# ece411-t15-light-sensitive-alarm-clock.net
KiCad netlist of a schematic drawn in EAGLE
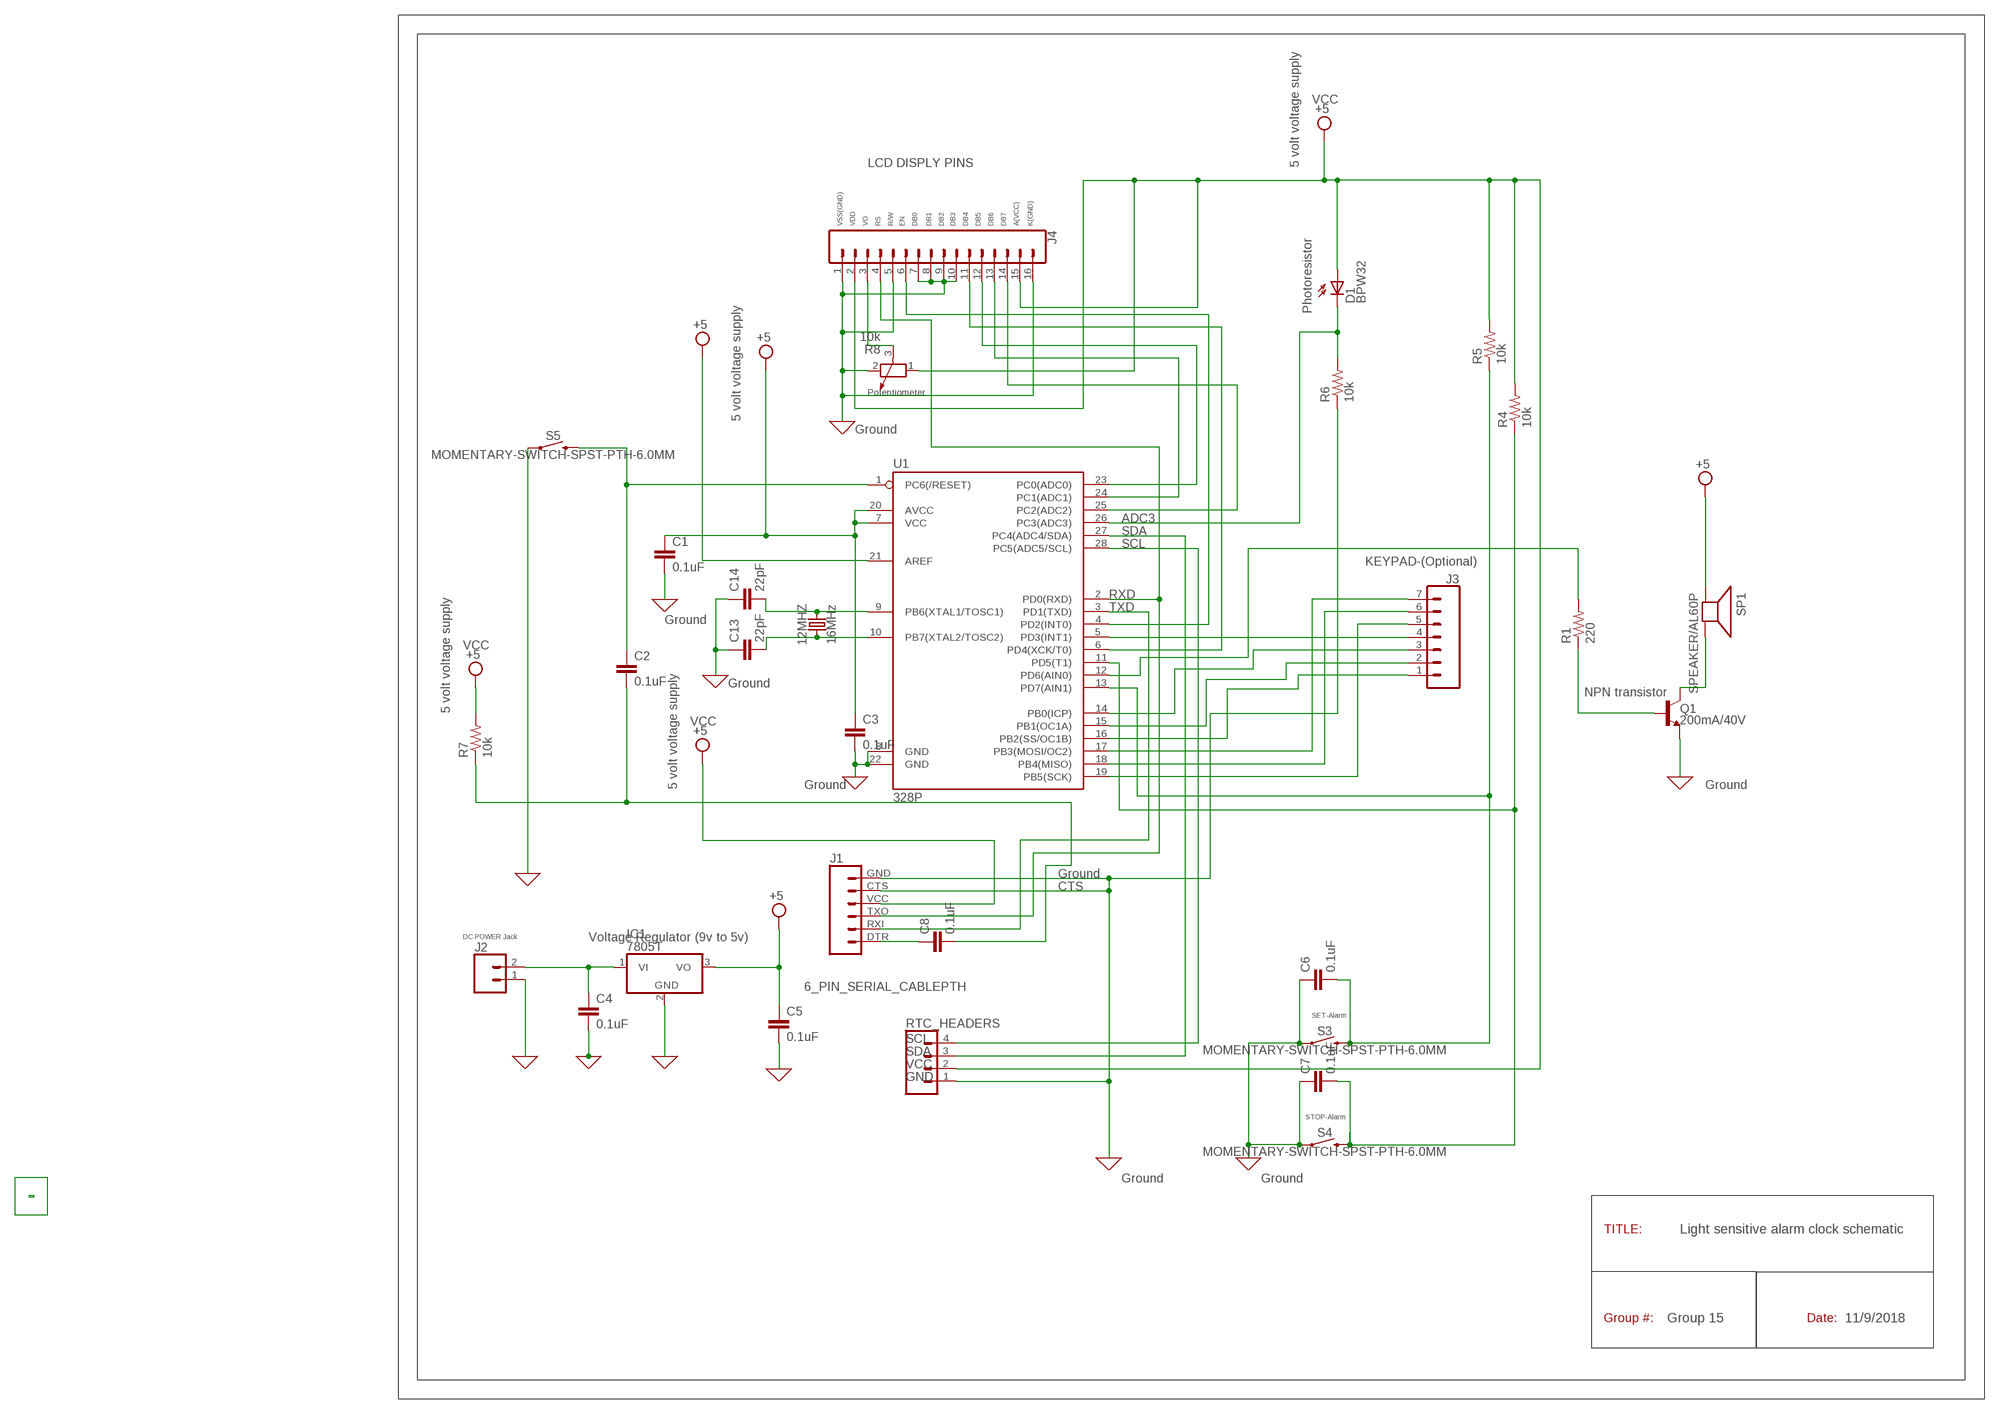
[diagram p0: schematic, sheet 1]

(export (version "E")
  (design (tool "Eeschema 10.0.6"))
  (components
    (comp (ref "12MHZ")
      (value "16MHz")
      (footprint "eagle-import:CRYSTAL-PTH-2X6-CYL")
      (libsource (lib "eagle-import") (part "CRYSTALPTH-2X6"))
    )
    (comp (ref "C1")
      (value "0.1uF")
      (footprint "eagle-import:0603")
      (libsource (lib "eagle-import") (part "0.1UF-0603-25V-(+80/-20%)"))
    )
    (comp (ref "C2")
      (value "0.1uF")
      (footprint "eagle-import:0603")
      (libsource (lib "eagle-import") (part "0.1UF-0603-25V-(+80/-20%)"))
    )
    (comp (ref "C3")
      (value "0.1uF")
      (footprint "eagle-import:0603")
      (libsource (lib "eagle-import") (part "0.1UF-0603-25V-(+80/-20%)"))
    )
    (comp (ref "C4")
      (value "0.1uF")
      (footprint "eagle-import:0603")
      (libsource (lib "eagle-import") (part "0.1UF-0603-25V-(+80/-20%)"))
    )
    (comp (ref "C5")
      (value "0.1uF")
      (footprint "eagle-import:0603")
      (libsource (lib "eagle-import") (part "0.1UF-0603-25V-(+80/-20%)"))
    )
    (comp (ref "C6")
      (value "0.1uF")
      (footprint "eagle-import:0603")
      (libsource (lib "eagle-import") (part "0.1UF-0603-25V-(+80/-20%)"))
    )
    (comp (ref "C7")
      (value "0.1uF")
      (footprint "eagle-import:0603")
      (libsource (lib "eagle-import") (part "0.1UF-0603-25V-(+80/-20%)"))
    )
    (comp (ref "C8")
      (value "0.1uF")
      (footprint "eagle-import:0603")
      (libsource (lib "eagle-import") (part "0.1UF-0603-25V-(+80/-20%)"))
    )
    (comp (ref "C13")
      (value "22pF")
      (footprint "eagle-import:0603")
      (libsource (lib "eagle-import") (part "22PF-0603-50V-5%"))
    )
    (comp (ref "C14")
      (value "22pF")
      (footprint "eagle-import:0603")
      (libsource (lib "eagle-import") (part "22PF-0603-50V-5%"))
    )
    (comp (ref "D1")
      (value "BPW32")
      (footprint "eagle-import:BPW32")
      (libsource (lib "eagle-import") (part "BPW32"))
    )
    (comp (ref "IC1")
      (value "7805T")
      (footprint "eagle-import:TO220H")
      (libsource (lib "eagle-import") (part "78T05"))
    )
    (comp (ref "J1")
      (value "6_PIN_SERIAL_CABLEPTH")
      (footprint "eagle-import:FTDI_BASIC")
      (libsource (lib "eagle-import") (part "6_PIN_SERIAL_CABLEPTH"))
    )
    (comp (ref "J2")
      (value "CONN_02")
      (footprint "eagle-import:1X02")
      (libsource (lib "eagle-import") (part "CONN_02"))
    )
    (comp (ref "J3")
      (value "CONN_07")
      (footprint "eagle-import:1X07")
      (libsource (lib "eagle-import") (part "CONN_07"))
    )
    (comp (ref "J4")
      (value "CONN_16")
      (footprint "eagle-import:1X16")
      (libsource (lib "eagle-import") (part "CONN_16"))
    )
    (comp (ref "Q1")
      (value "200mA/40V")
      (footprint "eagle-import:TO-92")
      (libsource (lib "eagle-import") (part "TRANS_NPN-2N3904"))
    )
    (comp (ref "R1")
      (value "220")
      (footprint "eagle-import:R0603")
      (libsource (lib "eagle-import") (part "R-US_R0603"))
    )
    (comp (ref "R4")
      (value "10k")
      (footprint "eagle-import:R0603")
      (libsource (lib "eagle-import") (part "R-US_R0603"))
    )
    (comp (ref "R5")
      (value "10k")
      (footprint "eagle-import:R0603")
      (libsource (lib "eagle-import") (part "R-US_R0603"))
    )
    (comp (ref "R6")
      (value "10k")
      (footprint "eagle-import:R0603")
      (libsource (lib "eagle-import") (part "R-US_R0603"))
    )
    (comp (ref "R7")
      (value "10k")
      (footprint "eagle-import:R0603")
      (libsource (lib "eagle-import") (part "R-US_R0603"))
    )
    (comp (ref "R8")
      (value "10k")
      (footprint "eagle-import:PT-10")
      (libsource (lib "eagle-import") (part "POTENTIOMETER_PT-10"))
    )
    (comp (ref "RTC_HEADERS")
      (value "CONN_04")
      (footprint "eagle-import:1X04")
      (libsource (lib "eagle-import") (part "CONN_04"))
    )
    (comp (ref "S3")
      (value "MOMENTARY-SWITCH-SPST-PTH-6.0MM")
      (footprint "eagle-import:TACTILE_SWITCH_PTH_6.0MM")
      (libsource (lib "eagle-import") (part "MOMENTARY-SWITCH-SPST-PTH-6.0MM"))
    )
    (comp (ref "S4")
      (value "MOMENTARY-SWITCH-SPST-PTH-6.0MM")
      (footprint "eagle-import:TACTILE_SWITCH_PTH_6.0MM")
      (libsource (lib "eagle-import") (part "MOMENTARY-SWITCH-SPST-PTH-6.0MM"))
    )
    (comp (ref "S5")
      (value "MOMENTARY-SWITCH-SPST-PTH-6.0MM")
      (footprint "eagle-import:TACTILE_SWITCH_PTH_6.0MM")
      (libsource (lib "eagle-import") (part "MOMENTARY-SWITCH-SPST-PTH-6.0MM"))
    )
    (comp (ref "SP1")
      (value "SPEAKER/AL60P")
      (footprint "eagle-import:AL60P")
      (libsource (lib "eagle-import") (part "SPEAKER/AL60P"))
    )
    (comp (ref "U1")
      (value "328P")
      (footprint "eagle-import:DIP28")
      (libsource (lib "eagle-import") (part "ATMEGA328P_PDIP"))
    )
  )
  (nets
    (net (code "1") (name "+5") (class "Default")
      (node (ref "C1") (pin "1") (pinfunction "1_1") (pintype "passive"))
      (node (ref "C3") (pin "1") (pinfunction "1_1") (pintype "passive"))
      (node (ref "C5") (pin "1") (pinfunction "1_1") (pintype "passive"))
      (node (ref "D1") (pin "A") (pinfunction "A_A") (pintype "passive"))
      (node (ref "IC1") (pin "3") (pinfunction "VO_3") (pintype "passive"))
      (node (ref "J1") (pin "VCC") (pinfunction "4_VCC") (pintype "passive"))
      (node (ref "J4") (pin "15") (pinfunction "15_15") (pintype "passive"))
      (node (ref "J4") (pin "2") (pinfunction "2_2") (pintype "passive"))
      (node (ref "R4") (pin "2") (pinfunction "2_2") (pintype "passive"))
      (node (ref "R5") (pin "2") (pinfunction "2_2") (pintype "passive"))
      (node (ref "R7") (pin "2") (pinfunction "2_2") (pintype "passive"))
      (node (ref "R8") (pin "1") (pinfunction "1_1") (pintype "passive"))
      (node (ref "RTC_HEADERS") (pin "2") (pinfunction "2_2") (pintype "passive"))
      (node (ref "SP1") (pin "1") (pinfunction "+_1") (pintype "passive"))
      (node (ref "U1") (pin "20") (pinfunction "AVCC_20") (pintype "bidirectional"))
      (node (ref "U1") (pin "21") (pinfunction "AREF_21") (pintype "bidirectional"))
      (node (ref "U1") (pin "7") (pinfunction "VCC_7") (pintype "bidirectional"))
    )
    (net (code "2") (name "GND") (class "Default")
      (node (ref "C1") (pin "2") (pinfunction "2_2") (pintype "passive"))
      (node (ref "C13") (pin "1") (pinfunction "1_1") (pintype "passive"))
      (node (ref "C14") (pin "1") (pinfunction "1_1") (pintype "passive"))
      (node (ref "C3") (pin "2") (pinfunction "2_2") (pintype "passive"))
      (node (ref "C4") (pin "2") (pinfunction "2_2") (pintype "passive"))
      (node (ref "C5") (pin "2") (pinfunction "2_2") (pintype "passive"))
      (node (ref "C6") (pin "1") (pinfunction "1_1") (pintype "passive"))
      (node (ref "C7") (pin "1") (pinfunction "1_1") (pintype "passive"))
      (node (ref "IC1") (pin "2") (pinfunction "GND_2") (pintype "passive"))
      (node (ref "J1") (pin "CTS") (pinfunction "5_CTS") (pintype "passive"))
      (node (ref "J1") (pin "GND") (pinfunction "6_GND") (pintype "passive"))
      (node (ref "J2") (pin "1") (pinfunction "1_1") (pintype "passive"))
      (node (ref "J4") (pin "1") (pinfunction "1_1") (pintype "passive"))
      (node (ref "J4") (pin "10") (pinfunction "10_10") (pintype "passive"))
      (node (ref "J4") (pin "16") (pinfunction "16_16") (pintype "passive"))
      (node (ref "J4") (pin "5") (pinfunction "5_5") (pintype "passive"))
      (node (ref "J4") (pin "7") (pinfunction "7_7") (pintype "passive"))
      (node (ref "J4") (pin "8") (pinfunction "8_8") (pintype "passive"))
      (node (ref "J4") (pin "9") (pinfunction "9_9") (pintype "passive"))
      (node (ref "Q1") (pin "1") (pinfunction "E_1") (pintype "passive"))
      (node (ref "R6") (pin "1") (pinfunction "1_1") (pintype "passive"))
      (node (ref "R8") (pin "2") (pinfunction "2_2") (pintype "passive"))
      (node (ref "RTC_HEADERS") (pin "1") (pinfunction "1_1") (pintype "passive"))
      (node (ref "S3") (pin "1") (pinfunction "1_1") (pintype "passive"))
      (node (ref "S4") (pin "1") (pinfunction "1_1") (pintype "passive"))
      (node (ref "S5") (pin "1") (pinfunction "1_1") (pintype "passive"))
      (node (ref "U1") (pin "22") (pinfunction "GND_22") (pintype "bidirectional"))
      (node (ref "U1") (pin "8") (pinfunction "GND_8") (pintype "bidirectional"))
    )
    (net (code "3") (name "Net-(C2-Pad2)") (class "Default")
      (node (ref "C2") (pin "2") (pinfunction "2_2") (pintype "passive"))
      (node (ref "C8") (pin "2") (pinfunction "2_2") (pintype "passive"))
      (node (ref "R7") (pin "1") (pinfunction "1_1") (pintype "passive"))
    )
    (net (code "4") (name "Net-(D1-C)") (class "Default")
      (node (ref "D1") (pin "K") (pinfunction "C_K") (pintype "passive"))
      (node (ref "R6") (pin "2") (pinfunction "2_2") (pintype "passive"))
      (node (ref "U1") (pin "26") (pinfunction "PC3(ADC3)_26") (pintype "bidirectional"))
    )
    (net (code "5") (name "Net-(IC1-VI)") (class "Default")
      (node (ref "C4") (pin "1") (pinfunction "1_1") (pintype "passive"))
      (node (ref "IC1") (pin "1") (pinfunction "VI_1") (pintype "input"))
      (node (ref "J2") (pin "2") (pinfunction "2_2") (pintype "passive"))
    )
    (net (code "6") (name "Net-(J1-1)") (class "Default")
      (node (ref "C8") (pin "1") (pinfunction "1_1") (pintype "passive"))
      (node (ref "J1") (pin "DTR") (pinfunction "1_DTR") (pintype "passive"))
    )
    (net (code "7") (name "Net-(J1-2)") (class "Default")
      (node (ref "J1") (pin "RXI") (pinfunction "2_RXI") (pintype "passive"))
      (node (ref "U1") (pin "3") (pinfunction "PD1(TXD)_3") (pintype "bidirectional"))
    )
    (net (code "8") (name "Net-(J1-3)") (class "Default")
      (node (ref "J1") (pin "TXO") (pinfunction "3_TXO") (pintype "passive"))
      (node (ref "J4") (pin "4") (pinfunction "4_4") (pintype "passive"))
      (node (ref "U1") (pin "2") (pinfunction "PD0(RXD)_2") (pintype "bidirectional"))
    )
    (net (code "9") (name "Net-(J4-Pad3)") (class "Default")
      (node (ref "J4") (pin "3") (pinfunction "3_3") (pintype "passive"))
      (node (ref "R8") (pin "3") (pinfunction "3_3") (pintype "passive"))
    )
    (net (code "10") (name "Net-(Q1-B)") (class "Default")
      (node (ref "Q1") (pin "2") (pinfunction "B_2") (pintype "passive"))
      (node (ref "R1") (pin "1") (pinfunction "1_1") (pintype "passive"))
    )
    (net (code "11") (name "Net-(Q1-C)") (class "Default")
      (node (ref "Q1") (pin "3") (pinfunction "C_3") (pintype "passive"))
      (node (ref "SP1") (pin "2") (pinfunction "-_2") (pintype "passive"))
    )
    (net (code "12") (name "Net-(S3-2)") (class "Default")
      (node (ref "C6") (pin "2") (pinfunction "2_2") (pintype "passive"))
      (node (ref "R5") (pin "1") (pinfunction "1_1") (pintype "passive"))
      (node (ref "S3") (pin "3") (pinfunction "2_3") (pintype "passive"))
      (node (ref "U1") (pin "13") (pinfunction "PD7(AIN1)_13") (pintype "bidirectional"))
    )
    (net (code "13") (name "Net-(S4-2)") (class "Default")
      (node (ref "C7") (pin "2") (pinfunction "2_2") (pintype "passive"))
      (node (ref "R4") (pin "1") (pinfunction "1_1") (pintype "passive"))
      (node (ref "S4") (pin "3") (pinfunction "2_3") (pintype "passive"))
      (node (ref "U1") (pin "11") (pinfunction "PD5(T1)_11") (pintype "bidirectional"))
    )
    (net (code "14") (name "Net-(S5-2)") (class "Default")
      (node (ref "C2") (pin "1") (pinfunction "1_1") (pintype "passive"))
      (node (ref "S5") (pin "3") (pinfunction "2_3") (pintype "passive"))
      (node (ref "U1") (pin "1") (pinfunction "PC6(/RESET)_1") (pintype "bidirectional"))
    )
    (net (code "15") (name "Net-(U1-PB0(ICP))") (class "Default")
      (node (ref "J3") (pin "3") (pinfunction "3_3") (pintype "passive"))
      (node (ref "U1") (pin "14") (pinfunction "PB0(ICP)_14") (pintype "bidirectional"))
    )
    (net (code "16") (name "Net-(U1-PB1(OC1A))") (class "Default")
      (node (ref "J3") (pin "2") (pinfunction "2_2") (pintype "passive"))
      (node (ref "U1") (pin "15") (pinfunction "PB1(OC1A)_15") (pintype "bidirectional"))
    )
    (net (code "17") (name "Net-(U1-PB2(SS{slash}OC1B))") (class "Default")
      (node (ref "J3") (pin "1") (pinfunction "1_1") (pintype "passive"))
      (node (ref "U1") (pin "16") (pinfunction "PB2(SS/OC1B)_16") (pintype "bidirectional"))
    )
    (net (code "18") (name "Net-(U1-PB3(MOSI{slash}OC2))") (class "Default")
      (node (ref "J3") (pin "7") (pinfunction "7_7") (pintype "passive"))
      (node (ref "U1") (pin "17") (pinfunction "PB3(MOSI/OC2)_17") (pintype "bidirectional"))
    )
    (net (code "19") (name "Net-(U1-PB4(MISO))") (class "Default")
      (node (ref "J3") (pin "6") (pinfunction "6_6") (pintype "passive"))
      (node (ref "U1") (pin "18") (pinfunction "PB4(MISO)_18") (pintype "bidirectional"))
    )
    (net (code "20") (name "Net-(U1-PB5(SCK))") (class "Default")
      (node (ref "J3") (pin "5") (pinfunction "5_5") (pintype "passive"))
      (node (ref "U1") (pin "19") (pinfunction "PB5(SCK)_19") (pintype "bidirectional"))
    )
    (net (code "21") (name "Net-(U1-PB6(XTAL1{slash}TOSC1))") (class "Default")
      (node (ref "12MHZ") (pin "2") (pinfunction "2_2") (pintype "passive"))
      (node (ref "C14") (pin "2") (pinfunction "2_2") (pintype "passive"))
      (node (ref "U1") (pin "9") (pinfunction "PB6(XTAL1/TOSC1)_9") (pintype "bidirectional"))
    )
    (net (code "22") (name "Net-(U1-PB7(XTAL2{slash}TOSC2))") (class "Default")
      (node (ref "12MHZ") (pin "1") (pinfunction "1_1") (pintype "passive"))
      (node (ref "C13") (pin "2") (pinfunction "2_2") (pintype "passive"))
      (node (ref "U1") (pin "10") (pinfunction "PB7(XTAL2/TOSC2)_10") (pintype "bidirectional"))
    )
    (net (code "23") (name "Net-(U1-PC0(ADC0))") (class "Default")
      (node (ref "J4") (pin "12") (pinfunction "12_12") (pintype "passive"))
      (node (ref "U1") (pin "23") (pinfunction "PC0(ADC0)_23") (pintype "bidirectional"))
    )
    (net (code "24") (name "Net-(U1-PC1(ADC1))") (class "Default")
      (node (ref "J4") (pin "13") (pinfunction "13_13") (pintype "passive"))
      (node (ref "U1") (pin "24") (pinfunction "PC1(ADC1)_24") (pintype "bidirectional"))
    )
    (net (code "25") (name "Net-(U1-PC2(ADC2))") (class "Default")
      (node (ref "J4") (pin "14") (pinfunction "14_14") (pintype "passive"))
      (node (ref "U1") (pin "25") (pinfunction "PC2(ADC2)_25") (pintype "bidirectional"))
    )
    (net (code "26") (name "Net-(U1-PC4(ADC4{slash}SDA))") (class "Default")
      (node (ref "RTC_HEADERS") (pin "3") (pinfunction "3_3") (pintype "passive"))
      (node (ref "U1") (pin "27") (pinfunction "PC4(ADC4/SDA)_27") (pintype "bidirectional"))
    )
    (net (code "27") (name "Net-(U1-PC5(ADC5{slash}SCL))") (class "Default")
      (node (ref "RTC_HEADERS") (pin "4") (pinfunction "4_4") (pintype "passive"))
      (node (ref "U1") (pin "28") (pinfunction "PC5(ADC5/SCL)_28") (pintype "bidirectional"))
    )
    (net (code "28") (name "Net-(U1-PD2(INT0))") (class "Default")
      (node (ref "J4") (pin "6") (pinfunction "6_6") (pintype "passive"))
      (node (ref "U1") (pin "4") (pinfunction "PD2(INT0)_4") (pintype "bidirectional"))
    )
    (net (code "29") (name "Net-(U1-PD3(INT1))") (class "Default")
      (node (ref "J3") (pin "4") (pinfunction "4_4") (pintype "passive"))
      (node (ref "U1") (pin "5") (pinfunction "PD3(INT1)_5") (pintype "bidirectional"))
    )
    (net (code "30") (name "Net-(U1-PD4(XCK{slash}T0))") (class "Default")
      (node (ref "J4") (pin "11") (pinfunction "11_11") (pintype "passive"))
      (node (ref "U1") (pin "6") (pinfunction "PD4(XCK/T0)_6") (pintype "bidirectional"))
    )
    (net (code "31") (name "Net-(U1-PD6(AIN0))") (class "Default")
      (node (ref "R1") (pin "2") (pinfunction "2_2") (pintype "passive"))
      (node (ref "U1") (pin "12") (pinfunction "PD6(AIN0)_12") (pintype "bidirectional"))
    )
  )
)
